# PPR_2_MP.net
KiCad netlist of a schematic drawn in EAGLE
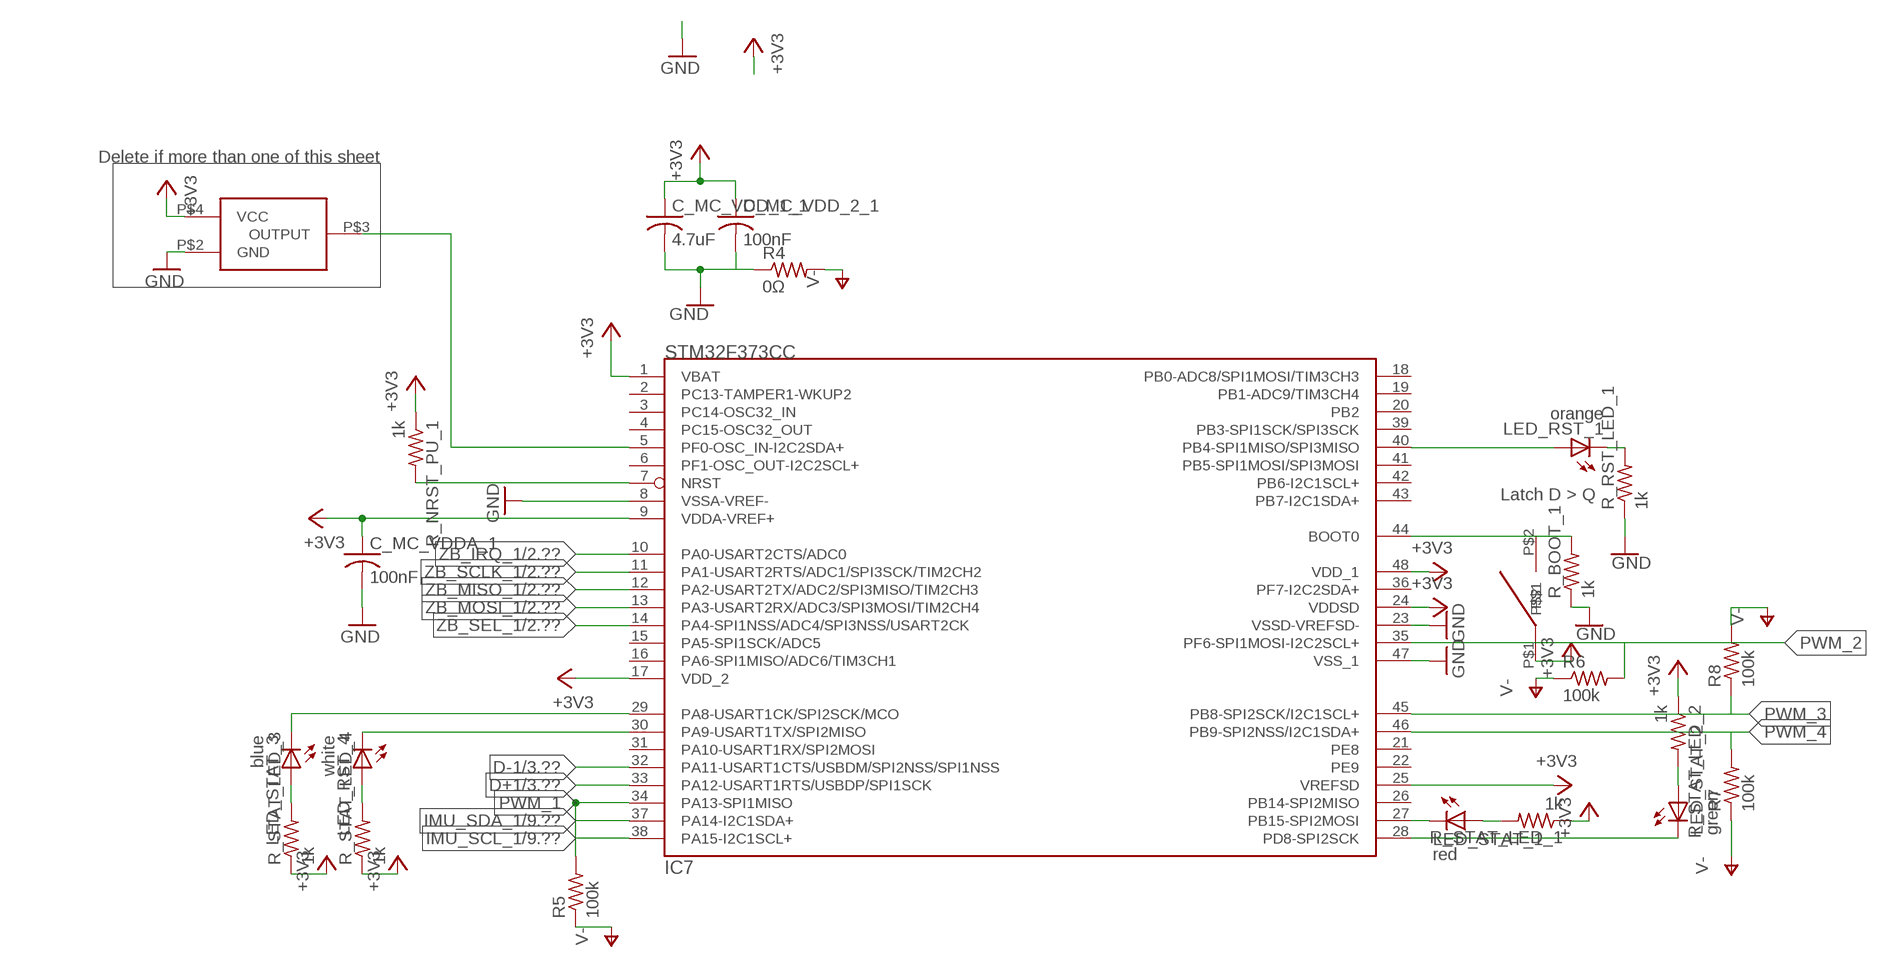
[diagram p0: schematic, sheet 1]
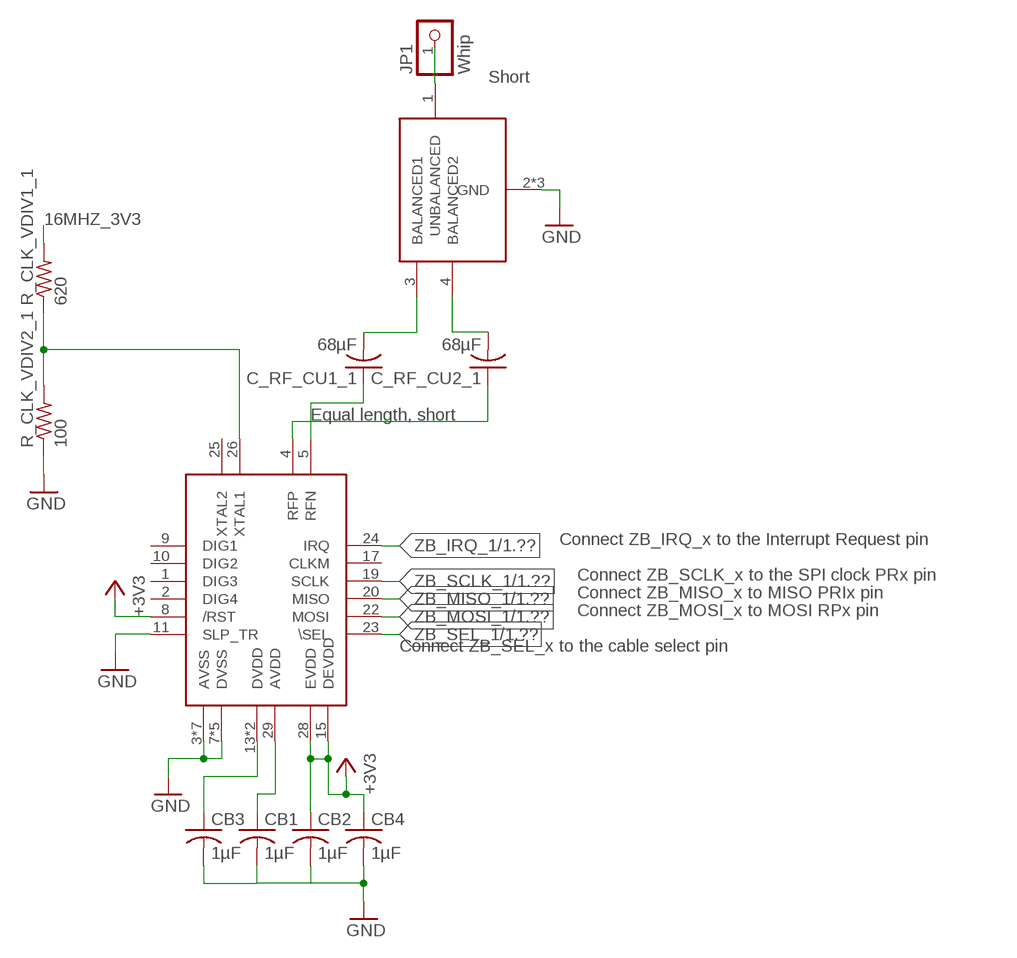
[diagram p1: schematic, sheet 2]
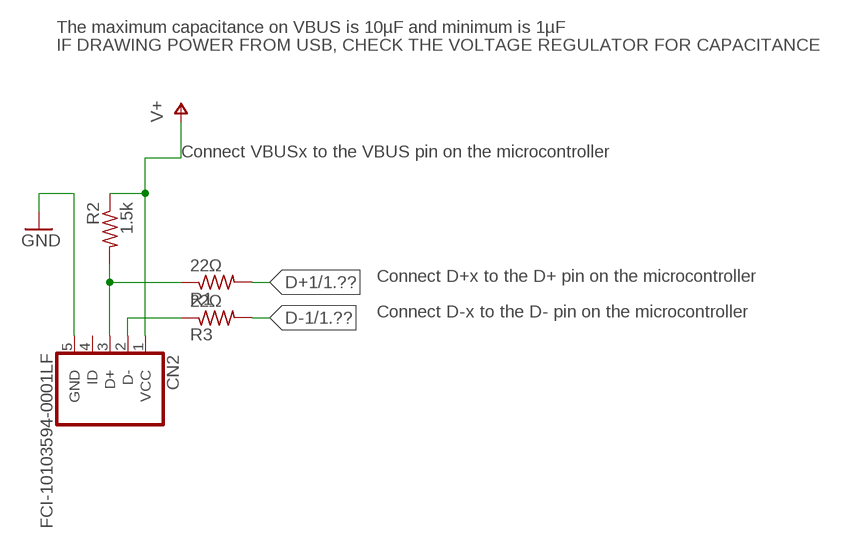
[diagram p2: schematic, sheet 3]
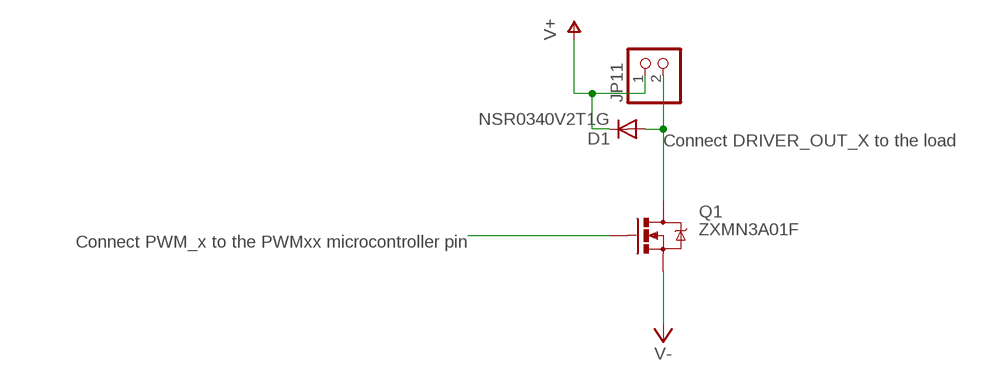
[diagram p3: schematic, sheet 4]
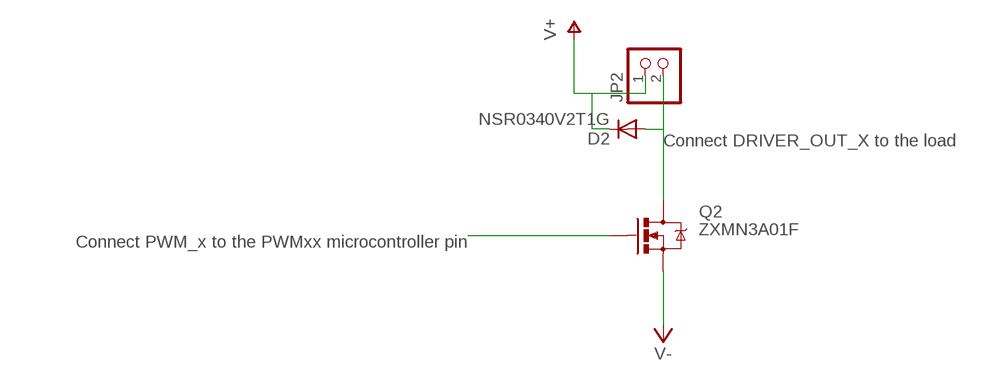
[diagram p4: schematic, sheet 5]
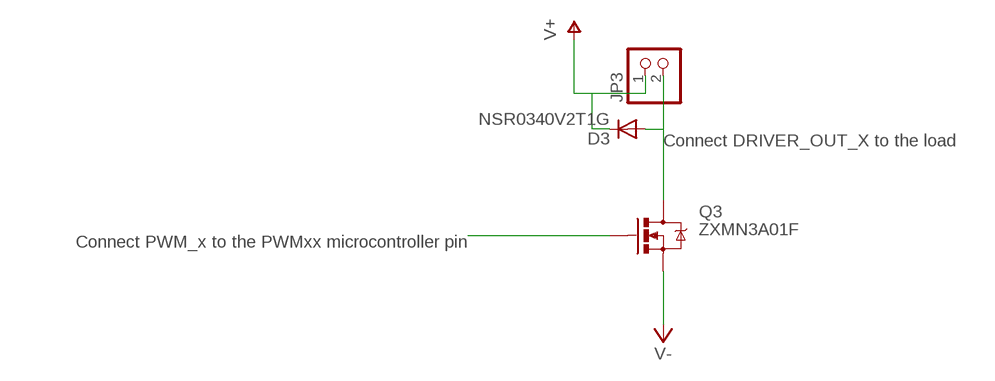
[diagram p5: schematic, sheet 6]
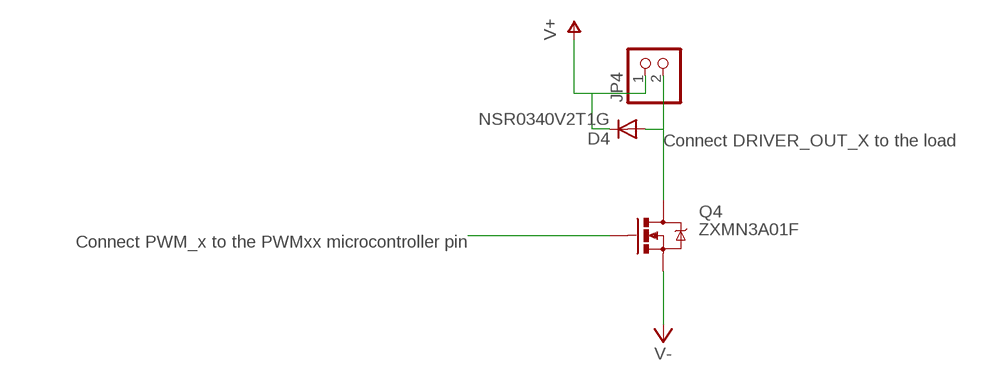
[diagram p6: schematic, sheet 7]
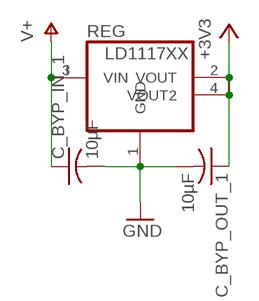
[diagram p7: schematic, sheet 8]
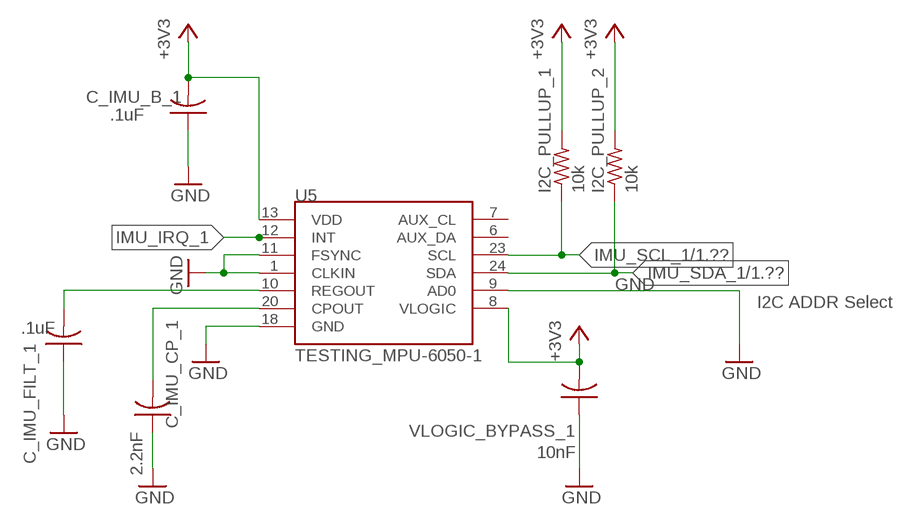
[diagram p8: schematic, sheet 9]
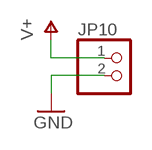
[diagram p9: schematic, sheet 10]

(export (version "E")
  (design (tool "Eeschema 10.0.6"))
  (components
    (comp (ref "C_IMU_B_1")
      (value ".1uF")
      (footprint "eagle-import:C0603")
      (libsource (lib "eagle-import") (part "C-USC0603"))
    )
    (comp (ref "C_IMU_CP_1")
      (value "2.2nF")
      (footprint "eagle-import:C0603")
      (libsource (lib "eagle-import") (part "C-USC0603"))
    )
    (comp (ref "C_IMU_FILT_1")
      (value ".1uF")
      (footprint "eagle-import:C0603")
      (libsource (lib "eagle-import") (part "C-USC0603"))
    )
    (comp (ref "I2C_PULLUP_1")
      (value "10k")
      (footprint "eagle-import:R0402")
      (libsource (lib "eagle-import") (part "R-US_R0402"))
    )
    (comp (ref "I2C_PULLUP_2")
      (value "10k")
      (footprint "eagle-import:R0402")
      (libsource (lib "eagle-import") (part "R-US_R0402"))
    )
    (comp (ref "U5")
      (value "TESTING_MPU-6050-1")
      (footprint "eagle-import:TESTING_QFN-24-4MM2")
      (libsource (lib "eagle-import") (part "TESTING_MPU-6050-1"))
    )
    (comp (ref "VLOGIC_BYPASS_1")
      (value "10nF")
      (footprint "eagle-import:C0603")
      (libsource (lib "eagle-import") (part "C-USC0603"))
    )
    (comp (ref "CN2")
      (value "FCI-10103594-0001LF")
      (footprint "eagle-import:FCI-10103594-0001LF")
      (libsource (lib "eagle-import") (part "USB-RECEPTABLE"))
    )
    (comp (ref "R1")
      (value "22Ω")
      (footprint "eagle-import:R0402")
      (libsource (lib "eagle-import") (part "resistor_R-US_R0402"))
    )
    (comp (ref "R2")
      (value "1.5k")
      (footprint "eagle-import:R0402")
      (libsource (lib "eagle-import") (part "resistor_R-US_R0402"))
    )
    (comp (ref "R3")
      (value "22Ω")
      (footprint "eagle-import:R0402")
      (libsource (lib "eagle-import") (part "resistor_R-US_R0402"))
    )
    (comp (ref "D1")
      (value "NSR0340V2T1G")
      (footprint "eagle-import:SOD523")
      (libsource (lib "eagle-import") (part "DIODE-SOD523"))
    )
    (comp (ref "JP11")
      (value "PINHD-1X2")
      (footprint "eagle-import:1X02")
      (libsource (lib "eagle-import") (part "PINHD-1X2"))
    )
    (comp (ref "Q1")
      (value "ZXMN3A01F")
      (footprint "eagle-import:SOT23-3")
      (libsource (lib "eagle-import") (part "MOSFET-NCHANNELSMD"))
    )
    (comp (ref "D4")
      (value "NSR0340V2T1G")
      (footprint "eagle-import:SOD523")
      (libsource (lib "eagle-import") (part "DIODE-SOD523"))
    )
    (comp (ref "JP4")
      (value "PINHD-1X2")
      (footprint "eagle-import:1X02")
      (libsource (lib "eagle-import") (part "PINHD-1X2"))
    )
    (comp (ref "Q4")
      (value "ZXMN3A01F")
      (footprint "eagle-import:SOT23-3")
      (libsource (lib "eagle-import") (part "MOSFET-NCHANNELSMD"))
    )
    (comp (ref "JP10")
      (value "PINHD-1X2")
      (footprint "eagle-import:1X02")
      (libsource (lib "eagle-import") (part "PINHD-1X2"))
    )
    (comp (ref "C_MC_VDDA_1")
      (value "100nF")
      (footprint "eagle-import:C0603")
      (libsource (lib "eagle-import") (part "C-USC0603"))
    )
    (comp (ref "C_MC_VDD_1_1")
      (value "4.7uF")
      (footprint "eagle-import:C0603")
      (libsource (lib "eagle-import") (part "C-USC0603"))
    )
    (comp (ref "C_MC_VDD_2_1")
      (value "100nF")
      (footprint "eagle-import:C0603")
      (libsource (lib "eagle-import") (part "C-USC0603"))
    )
    (comp (ref "IC7")
      (value "STM32F373CC")
      (footprint "eagle-import:LQFP48")
      (libsource (lib "eagle-import") (part "STM32F373CC"))
    )
    (comp (ref "LED_RST_1")
      (value "orange")
      (footprint "eagle-import:CHIPLED_0603")
      (libsource (lib "eagle-import") (part "LEDCHIPLED_0603"))
    )
    (comp (ref "LED_RST_4")
      (value "white")
      (footprint "eagle-import:CHIPLED_0603")
      (libsource (lib "eagle-import") (part "LEDCHIPLED_0603"))
    )
    (comp (ref "LED_STAT_1")
      (value "red")
      (footprint "eagle-import:CHIPLED_0603")
      (libsource (lib "eagle-import") (part "LEDCHIPLED_0603"))
    )
    (comp (ref "LED_STAT_2")
      (value "green")
      (footprint "eagle-import:CHIPLED_0603")
      (libsource (lib "eagle-import") (part "LEDCHIPLED_0603"))
    )
    (comp (ref "LED_STAT_3")
      (value "blue")
      (footprint "eagle-import:CHIPLED_0603")
      (libsource (lib "eagle-import") (part "LEDCHIPLED_0603"))
    )
    (comp (ref "OSC1")
      (value "FOX924B")
      (footprint "eagle-import:4-SMD_5X3.2")
      (libsource (lib "eagle-import") (part "FOX924B"))
    )
    (comp (ref "R4")
      (value "0Ω")
      (footprint "eagle-import:R0603")
      (libsource (lib "eagle-import") (part "resistor_R-US_R0603"))
    )
    (comp (ref "R5")
      (value "100k")
      (footprint "eagle-import:R0603")
      (libsource (lib "eagle-import") (part "resistor_R-US_R0603"))
    )
    (comp (ref "R6")
      (value "100k")
      (footprint "eagle-import:R0603")
      (libsource (lib "eagle-import") (part "resistor_R-US_R0603"))
    )
    (comp (ref "R7")
      (value "100k")
      (footprint "eagle-import:R0603")
      (libsource (lib "eagle-import") (part "resistor_R-US_R0603"))
    )
    (comp (ref "R8")
      (value "100k")
      (footprint "eagle-import:R0603")
      (libsource (lib "eagle-import") (part "resistor_R-US_R0603"))
    )
    (comp (ref "R_BOOT_1")
      (value "1k")
      (footprint "eagle-import:R0603")
      (libsource (lib "eagle-import") (part "resistor_R-US_R0603"))
    )
    (comp (ref "R_NRST_PU_1")
      (value "1k")
      (footprint "eagle-import:R0603")
      (libsource (lib "eagle-import") (part "resistor_R-US_R0603"))
    )
    (comp (ref "R_RST_LED_1")
      (value "1k")
      (footprint "eagle-import:R0603")
      (libsource (lib "eagle-import") (part "resistor_R-US_R0603"))
    )
    (comp (ref "R_STAT_LED_1")
      (value "1k")
      (footprint "eagle-import:R0603")
      (libsource (lib "eagle-import") (part "resistor_R-US_R0603"))
    )
    (comp (ref "R_STAT_LED_2")
      (value "1k")
      (footprint "eagle-import:R0603")
      (libsource (lib "eagle-import") (part "resistor_R-US_R0603"))
    )
    (comp (ref "R_STAT_LED_3")
      (value "1k")
      (footprint "eagle-import:R0603")
      (libsource (lib "eagle-import") (part "resistor_R-US_R0603"))
    )
    (comp (ref "R_STAT_LED_4")
      (value "1k")
      (footprint "eagle-import:R0603")
      (libsource (lib "eagle-import") (part "resistor_R-US_R0603"))
    )
    (comp (ref "SW1")
      (value "B3U")
      (footprint "eagle-import:B3U")
      (libsource (lib "eagle-import") (part "B3U"))
    )
    (comp (ref "C_BYP_IN_1")
      (value "10µF")
      (footprint "eagle-import:C1206")
      (libsource (lib "eagle-import") (part "C-USC1206"))
    )
    (comp (ref "C_BYP_OUT_1")
      (value "10µF")
      (footprint "eagle-import:C0603")
      (libsource (lib "eagle-import") (part "C-USC0603"))
    )
    (comp (ref "REG")
      (value "LD1117XX")
      (footprint "eagle-import:SOT-223")
      (libsource (lib "eagle-import") (part "LD1117XX"))
    )
    (comp (ref "BALUN1")
      (value "0896FB15A0100")
      (footprint "eagle-import:0896FB15A0100")
      (libsource (lib "eagle-import") (part "0896FB15A0100"))
    )
    (comp (ref "CB1")
      (value "1µF")
      (footprint "eagle-import:C0603")
      (libsource (lib "eagle-import") (part "C-USC0603"))
    )
    (comp (ref "CB2")
      (value "1µF")
      (footprint "eagle-import:C0603")
      (libsource (lib "eagle-import") (part "C-USC0603"))
    )
    (comp (ref "CB3")
      (value "1µF")
      (footprint "eagle-import:C0603")
      (libsource (lib "eagle-import") (part "C-USC0603"))
    )
    (comp (ref "CB4")
      (value "1µF")
      (footprint "eagle-import:C0603")
      (libsource (lib "eagle-import") (part "C-USC0603"))
    )
    (comp (ref "C_RF_CU1_1")
      (value "68µF")
      (footprint "eagle-import:C0603")
      (libsource (lib "eagle-import") (part "C-USC0603"))
    )
    (comp (ref "C_RF_CU2_1")
      (value "68µF")
      (footprint "eagle-import:C0603")
      (libsource (lib "eagle-import") (part "C-USC0603"))
    )
    (comp (ref "JP1")
      (value "Whip")
      (footprint "eagle-import:1X01M")
      (libsource (lib "eagle-import") (part "PINHD-1X01_2.00"))
    )
    (comp (ref "RADIO1")
      (value "AT86RF")
      (footprint "eagle-import:QFNN32")
      (libsource (lib "eagle-import") (part "AT86RF"))
    )
    (comp (ref "R_CLK_VDIV1_1")
      (value "620")
      (footprint "eagle-import:R0603")
      (libsource (lib "eagle-import") (part "resistor_R-US_R0603"))
    )
    (comp (ref "R_CLK_VDIV2_1")
      (value "100")
      (footprint "eagle-import:R0603")
      (libsource (lib "eagle-import") (part "resistor_R-US_R0603"))
    )
    (comp (ref "D3")
      (value "NSR0340V2T1G")
      (footprint "eagle-import:SOD523")
      (libsource (lib "eagle-import") (part "DIODE-SOD523"))
    )
    (comp (ref "JP3")
      (value "PINHD-1X2")
      (footprint "eagle-import:1X02")
      (libsource (lib "eagle-import") (part "PINHD-1X2"))
    )
    (comp (ref "Q3")
      (value "ZXMN3A01F")
      (footprint "eagle-import:SOT23-3")
      (libsource (lib "eagle-import") (part "MOSFET-NCHANNELSMD"))
    )
    (comp (ref "D2")
      (value "NSR0340V2T1G")
      (footprint "eagle-import:SOD523")
      (libsource (lib "eagle-import") (part "DIODE-SOD523"))
    )
    (comp (ref "JP2")
      (value "PINHD-1X2")
      (footprint "eagle-import:1X02")
      (libsource (lib "eagle-import") (part "PINHD-1X2"))
    )
    (comp (ref "Q2")
      (value "ZXMN3A01F")
      (footprint "eagle-import:SOT23-3")
      (libsource (lib "eagle-import") (part "MOSFET-NCHANNELSMD"))
    )
  )
  (nets
    (net (code "1") (name "+3V3") (class "Default")
      (node (ref "CB2") (pin "1") (pinfunction "1_1") (pintype "passive"))
      (node (ref "CB4") (pin "1") (pinfunction "1_1") (pintype "passive"))
      (node (ref "C_BYP_OUT_1") (pin "1") (pinfunction "1_1") (pintype "passive"))
      (node (ref "C_IMU_B_1") (pin "2") (pinfunction "2_2") (pintype "passive"))
      (node (ref "C_MC_VDDA_1") (pin "1") (pinfunction "1_1") (pintype "passive"))
      (node (ref "C_MC_VDD_1_1") (pin "1") (pinfunction "1_1") (pintype "passive"))
      (node (ref "C_MC_VDD_2_1") (pin "1") (pinfunction "1_1") (pintype "passive"))
      (node (ref "I2C_PULLUP_1") (pin "2") (pinfunction "2_2") (pintype "passive"))
      (node (ref "I2C_PULLUP_2") (pin "2") (pinfunction "2_2") (pintype "passive"))
      (node (ref "IC7") (pin "1") (pinfunction "VBAT_1") (pintype "power_in"))
      (node (ref "IC7") (pin "17") (pinfunction "VDD_2_17") (pintype "bidirectional"))
      (node (ref "IC7") (pin "24") (pinfunction "VDDSD_24") (pintype "power_in"))
      (node (ref "IC7") (pin "25") (pinfunction "VREFSD_25") (pintype "bidirectional"))
      (node (ref "IC7") (pin "48") (pinfunction "VDD_1_48") (pintype "power_in"))
      (node (ref "IC7") (pin "9") (pinfunction "VDDA-VREF+_9") (pintype "power_in"))
      (node (ref "OSC1") (pin "P$4") (pinfunction "VCC_P$4") (pintype "bidirectional"))
      (node (ref "RADIO1") (pin "15") (pinfunction "DEVDD_15") (pintype "power_in"))
      (node (ref "RADIO1") (pin "28") (pinfunction "EVDD_28") (pintype "power_in"))
      (node (ref "RADIO1") (pin "8") (pinfunction "/RST_8") (pintype "input"))
      (node (ref "REG") (pin "2") (pinfunction "VOUT_2") (pintype "output"))
      (node (ref "REG") (pin "4") (pinfunction "VOUT2_4") (pintype "output"))
      (node (ref "R_NRST_PU_1") (pin "1") (pinfunction "1_1") (pintype "passive"))
      (node (ref "R_STAT_LED_1") (pin "1") (pinfunction "1_1") (pintype "passive"))
      (node (ref "R_STAT_LED_2") (pin "1") (pinfunction "1_1") (pintype "passive"))
      (node (ref "R_STAT_LED_3") (pin "1") (pinfunction "1_1") (pintype "passive"))
      (node (ref "R_STAT_LED_4") (pin "1") (pinfunction "1_1") (pintype "passive"))
      (node (ref "SW1") (pin "P$1") (pinfunction "P$1_P$1") (pintype "bidirectional"))
      (node (ref "U5") (pin "13") (pinfunction "VDD_13") (pintype "bidirectional"))
      (node (ref "U5") (pin "8") (pinfunction "VLOGIC_8") (pintype "bidirectional"))
      (node (ref "VLOGIC_BYPASS_1") (pin "2") (pinfunction "2_2") (pintype "passive"))
    )
    (net (code "2") (name "16MHZ_3V3") (class "Default")
      (node (ref "IC7") (pin "5") (pinfunction "PF0-OSC_IN-I2C2SDA+_5") (pintype "bidirectional"))
      (node (ref "OSC1") (pin "P$3") (pinfunction "OUTPUT_P$3") (pintype "bidirectional"))
      (node (ref "R_CLK_VDIV1_1") (pin "2") (pinfunction "2_2") (pintype "passive"))
    )
    (net (code "3") (name "D+1") (class "Default")
      (node (ref "IC7") (pin "33") (pinfunction "PA12-USART1RTS/USBDP/SPI1SCK_33") (pintype "bidirectional"))
      (node (ref "R1") (pin "2") (pinfunction "2_2") (pintype "passive"))
    )
    (net (code "4") (name "D-1") (class "Default")
      (node (ref "IC7") (pin "32") (pinfunction "PA11-USART1CTS/USBDM/SPI2NSS/SPI1NSS_32") (pintype "bidirectional"))
      (node (ref "R3") (pin "2") (pinfunction "2_2") (pintype "passive"))
    )
    (net (code "5") (name "GND") (class "Default")
      (node (ref "BALUN1") (pin "2") (pinfunction "GND_2") (pintype "power_in"))
      (node (ref "BALUN1") (pin "5") (pinfunction "GND_5") (pintype "power_in"))
      (node (ref "BALUN1") (pin "6") (pinfunction "GND_6") (pintype "power_in"))
      (node (ref "CB1") (pin "2") (pinfunction "2_2") (pintype "passive"))
      (node (ref "CB2") (pin "2") (pinfunction "2_2") (pintype "passive"))
      (node (ref "CB3") (pin "2") (pinfunction "2_2") (pintype "passive"))
      (node (ref "CB4") (pin "2") (pinfunction "2_2") (pintype "passive"))
      (node (ref "CN2") (pin "5") (pinfunction "GND_5") (pintype "bidirectional"))
      (node (ref "C_BYP_IN_1") (pin "2") (pinfunction "2_2") (pintype "passive"))
      (node (ref "C_BYP_OUT_1") (pin "2") (pinfunction "2_2") (pintype "passive"))
      (node (ref "C_IMU_B_1") (pin "1") (pinfunction "1_1") (pintype "passive"))
      (node (ref "C_IMU_CP_1") (pin "1") (pinfunction "1_1") (pintype "passive"))
      (node (ref "C_IMU_FILT_1") (pin "1") (pinfunction "1_1") (pintype "passive"))
      (node (ref "C_MC_VDDA_1") (pin "2") (pinfunction "2_2") (pintype "passive"))
      (node (ref "C_MC_VDD_1_1") (pin "2") (pinfunction "2_2") (pintype "passive"))
      (node (ref "C_MC_VDD_2_1") (pin "2") (pinfunction "2_2") (pintype "passive"))
      (node (ref "IC7") (pin "23") (pinfunction "VSSD-VREFSD-_23") (pintype "power_in"))
      (node (ref "IC7") (pin "47") (pinfunction "VSS_1_47") (pintype "power_in"))
      (node (ref "IC7") (pin "8") (pinfunction "VSSA-VREF-_8") (pintype "power_in"))
      (node (ref "JP10") (pin "2") (pinfunction "2_2") (pintype "passive"))
      (node (ref "OSC1") (pin "P$2") (pinfunction "GND_P$2") (pintype "bidirectional"))
      (node (ref "R4") (pin "1") (pinfunction "1_1") (pintype "passive"))
      (node (ref "RADIO1") (pin "11") (pinfunction "SLP_TR_11") (pintype "bidirectional"))
      (node (ref "RADIO1") (pin "12") (pinfunction "DVSS_12") (pintype "power_in"))
      (node (ref "RADIO1") (pin "16") (pinfunction "DVSS_16") (pintype "power_in"))
      (node (ref "RADIO1") (pin "18") (pinfunction "DVSS_18") (pintype "power_in"))
      (node (ref "RADIO1") (pin "21") (pinfunction "DVSS_21") (pintype "power_in"))
      (node (ref "RADIO1") (pin "27") (pinfunction "AVSS_27") (pintype "power_in"))
      (node (ref "RADIO1") (pin "3") (pinfunction "AVSS_3") (pintype "power_in"))
      (node (ref "RADIO1") (pin "30") (pinfunction "AVSS_30") (pintype "power_in"))
      (node (ref "RADIO1") (pin "31") (pinfunction "AVSS_31") (pintype "power_in"))
      (node (ref "RADIO1") (pin "32") (pinfunction "AVSS_32") (pintype "power_in"))
      (node (ref "RADIO1") (pin "6") (pinfunction "AVSS_6") (pintype "power_in"))
      (node (ref "RADIO1") (pin "7") (pinfunction "DVSS_7") (pintype "power_in"))
      (node (ref "RADIO1") (pin "EXP") (pinfunction "AVSS_EXP") (pintype "power_in"))
      (node (ref "REG") (pin "1") (pinfunction "GND_1") (pintype "power_in"))
      (node (ref "R_BOOT_1") (pin "1") (pinfunction "1_1") (pintype "passive"))
      (node (ref "R_CLK_VDIV2_1") (pin "1") (pinfunction "1_1") (pintype "passive"))
      (node (ref "R_RST_LED_1") (pin "1") (pinfunction "1_1") (pintype "passive"))
      (node (ref "U5") (pin "1") (pinfunction "CLKIN_1") (pintype "bidirectional"))
      (node (ref "U5") (pin "11") (pinfunction "FSYNC_11") (pintype "bidirectional"))
      (node (ref "U5") (pin "18") (pinfunction "GND_18") (pintype "bidirectional"))
      (node (ref "U5") (pin "9") (pinfunction "AD0_9") (pintype "bidirectional"))
      (node (ref "VLOGIC_BYPASS_1") (pin "1") (pinfunction "1_1") (pintype "passive"))
    )
    (net (code "6") (name "IMU_IRQ_1") (class "Default")
      (node (ref "U5") (pin "12") (pinfunction "INT_12") (pintype "bidirectional"))
    )
    (net (code "7") (name "IMU_SCL_1") (class "Default")
      (node (ref "I2C_PULLUP_1") (pin "1") (pinfunction "1_1") (pintype "passive"))
      (node (ref "IC7") (pin "38") (pinfunction "PA15-I2C1SCL+_38") (pintype "bidirectional"))
      (node (ref "U5") (pin "23") (pinfunction "SCL_23") (pintype "bidirectional"))
    )
    (net (code "8") (name "IMU_SDA_1") (class "Default")
      (node (ref "I2C_PULLUP_2") (pin "1") (pinfunction "1_1") (pintype "passive"))
      (node (ref "IC7") (pin "37") (pinfunction "PA14-I2C1SDA+_37") (pintype "bidirectional"))
      (node (ref "U5") (pin "24") (pinfunction "SDA_24") (pintype "bidirectional"))
    )
    (net (code "9") (name "Net-(BALUN1-BALANCED1)") (class "Default")
      (node (ref "BALUN1") (pin "3") (pinfunction "BALANCED1_3") (pintype "bidirectional"))
      (node (ref "C_RF_CU1_1") (pin "2") (pinfunction "2_2") (pintype "passive"))
    )
    (net (code "10") (name "Net-(BALUN1-BALANCED2)") (class "Default")
      (node (ref "BALUN1") (pin "4") (pinfunction "BALANCED2_4") (pintype "bidirectional"))
      (node (ref "C_RF_CU2_1") (pin "2") (pinfunction "2_2") (pintype "passive"))
    )
    (net (code "11") (name "Net-(BALUN1-UNBALANCED)") (class "Default")
      (node (ref "BALUN1") (pin "1") (pinfunction "UNBALANCED_1") (pintype "bidirectional"))
      (node (ref "JP1") (pin "1") (pinfunction "1_1") (pintype "passive"))
    )
    (net (code "12") (name "Net-(CB3-Pad1)") (class "Default")
      (node (ref "CB3") (pin "1") (pinfunction "1_1") (pintype "passive"))
      (node (ref "RADIO1") (pin "13") (pinfunction "DVDD_13") (pintype "power_in"))
      (node (ref "RADIO1") (pin "14") (pinfunction "DVDD_14") (pintype "power_in"))
    )
    (net (code "13") (name "Net-(CN2-D+)") (class "Default")
      (node (ref "CN2") (pin "3") (pinfunction "D+_3") (pintype "bidirectional"))
      (node (ref "R1") (pin "1") (pinfunction "1_1") (pintype "passive"))
      (node (ref "R2") (pin "2") (pinfunction "2_2") (pintype "passive"))
    )
    (net (code "14") (name "Net-(CN2-D-)") (class "Default")
      (node (ref "CN2") (pin "2") (pinfunction "D-_2") (pintype "bidirectional"))
      (node (ref "R3") (pin "1") (pinfunction "1_1") (pintype "passive"))
    )
    (net (code "15") (name "Net-(IC7-BOOT0)") (class "Default")
      (node (ref "IC7") (pin "44") (pinfunction "BOOT0_44") (pintype "input"))
      (node (ref "R_BOOT_1") (pin "2") (pinfunction "2_2") (pintype "passive"))
      (node (ref "SW1") (pin "P$2") (pinfunction "P$2_P$2") (pintype "bidirectional"))
    )
    (net (code "16") (name "Net-(IC7-NRST)") (class "Default")
      (node (ref "IC7") (pin "7") (pinfunction "NRST_7") (pintype "bidirectional"))
      (node (ref "R_NRST_PU_1") (pin "2") (pinfunction "2_2") (pintype "passive"))
    )
    (net (code "17") (name "Net-(IC7-PA8-USART1CK{slash}SPI2SCK{slash}MCO)") (class "Default")
      (node (ref "IC7") (pin "29") (pinfunction "PA8-USART1CK/SPI2SCK/MCO_29") (pintype "bidirectional"))
      (node (ref "LED_STAT_3") (pin "C") (pinfunction "C_C") (pintype "passive"))
    )
    (net (code "18") (name "Net-(IC7-PA9-USART1TX{slash}SPI2MISO)") (class "Default")
      (node (ref "IC7") (pin "30") (pinfunction "PA9-USART1TX/SPI2MISO_30") (pintype "bidirectional"))
      (node (ref "LED_RST_4") (pin "C") (pinfunction "C_C") (pintype "passive"))
    )
    (net (code "19") (name "Net-(IC7-PB4-SPI1MISO{slash}SPI3MISO)") (class "Default")
      (node (ref "IC7") (pin "40") (pinfunction "PB4-SPI1MISO/SPI3MISO_40") (pintype "bidirectional"))
      (node (ref "LED_RST_1") (pin "A") (pinfunction "A_A") (pintype "passive"))
    )
    (net (code "20") (name "Net-(IC7-PB15-SPI2MOSI)") (class "Default")
      (node (ref "IC7") (pin "27") (pinfunction "PB15-SPI2MOSI_27") (pintype "bidirectional"))
      (node (ref "LED_STAT_1") (pin "C") (pinfunction "C_C") (pintype "passive"))
    )
    (net (code "21") (name "Net-(IC7-PD8-SPI2SCK)") (class "Default")
      (node (ref "IC7") (pin "28") (pinfunction "PD8-SPI2SCK_28") (pintype "bidirectional"))
      (node (ref "LED_STAT_2") (pin "C") (pinfunction "C_C") (pintype "passive"))
    )
    (net (code "22") (name "Net-(LED_RST_1-PadC)") (class "Default")
      (node (ref "LED_RST_1") (pin "C") (pinfunction "C_C") (pintype "passive"))
      (node (ref "R_RST_LED_1") (pin "2") (pinfunction "2_2") (pintype "passive"))
    )
    (net (code "23") (name "Net-(LED_RST_4-PadA)") (class "Default")
      (node (ref "LED_RST_4") (pin "A") (pinfunction "A_A") (pintype "passive"))
      (node (ref "R_STAT_LED_4") (pin "2") (pinfunction "2_2") (pintype "passive"))
    )
    (net (code "24") (name "Net-(LED_STAT_1-PadA)") (class "Default")
      (node (ref "LED_STAT_1") (pin "A") (pinfunction "A_A") (pintype "passive"))
      (node (ref "R_STAT_LED_1") (pin "2") (pinfunction "2_2") (pintype "passive"))
    )
    (net (code "25") (name "Net-(LED_STAT_2-PadA)") (class "Default")
      (node (ref "LED_STAT_2") (pin "A") (pinfunction "A_A") (pintype "passive"))
      (node (ref "R_STAT_LED_2") (pin "2") (pinfunction "2_2") (pintype "passive"))
    )
    (net (code "26") (name "Net-(LED_STAT_3-PadA)") (class "Default")
      (node (ref "LED_STAT_3") (pin "A") (pinfunction "A_A") (pintype "passive"))
      (node (ref "R_STAT_LED_3") (pin "2") (pinfunction "2_2") (pintype "passive"))
    )
    (net (code "27") (name "Net-(Q1-D)") (class "Default")
      (node (ref "D1") (pin "A") (pinfunction "A_A") (pintype "passive"))
      (node (ref "JP11") (pin "2") (pinfunction "2_2") (pintype "passive"))
      (node (ref "Q1") (pin "3") (pinfunction "D_3") (pintype "passive"))
    )
    (net (code "28") (name "Net-(Q2-D)") (class "Default")
      (node (ref "D2") (pin "A") (pinfunction "A_A") (pintype "passive"))
      (node (ref "JP2") (pin "2") (pinfunction "2_2") (pintype "passive"))
      (node (ref "Q2") (pin "3") (pinfunction "D_3") (pintype "passive"))
    )
    (net (code "29") (name "Net-(Q3-D)") (class "Default")
      (node (ref "D3") (pin "A") (pinfunction "A_A") (pintype "passive"))
      (node (ref "JP3") (pin "2") (pinfunction "2_2") (pintype "passive"))
      (node (ref "Q3") (pin "3") (pinfunction "D_3") (pintype "passive"))
    )
    (net (code "30") (name "Net-(Q4-D)") (class "Default")
      (node (ref "D4") (pin "A") (pinfunction "A_A") (pintype "passive"))
      (node (ref "JP4") (pin "2") (pinfunction "2_2") (pintype "passive"))
      (node (ref "Q4") (pin "3") (pinfunction "D_3") (pintype "passive"))
    )
    (net (code "31") (name "Net-(RADIO1-AVDD)") (class "Default")
      (node (ref "CB1") (pin "1") (pinfunction "1_1") (pintype "passive"))
      (node (ref "RADIO1") (pin "29") (pinfunction "AVDD_29") (pintype "power_in"))
    )
    (net (code "32") (name "Net-(RADIO1-RFN)") (class "Default")
      (node (ref "C_RF_CU1_1") (pin "1") (pinfunction "1_1") (pintype "passive"))
      (node (ref "RADIO1") (pin "5") (pinfunction "RFN_5") (pintype "bidirectional"))
    )
    (net (code "33") (name "Net-(RADIO1-RFP)") (class "Default")
      (node (ref "C_RF_CU2_1") (pin "1") (pinfunction "1_1") (pintype "passive"))
      (node (ref "RADIO1") (pin "4") (pinfunction "RFP_4") (pintype "bidirectional"))
    )
    (net (code "34") (name "Net-(RADIO1-XTAL1)") (class "Default")
      (node (ref "RADIO1") (pin "26") (pinfunction "XTAL1_26") (pintype "bidirectional"))
      (node (ref "R_CLK_VDIV1_1") (pin "1") (pinfunction "1_1") (pintype "passive"))
      (node (ref "R_CLK_VDIV2_1") (pin "2") (pinfunction "2_2") (pintype "passive"))
    )
    (net (code "35") (name "Net-(U5-CPOUT)") (class "Default")
      (node (ref "C_IMU_CP_1") (pin "2") (pinfunction "2_2") (pintype "passive"))
      (node (ref "U5") (pin "20") (pinfunction "CPOUT_20") (pintype "bidirectional"))
    )
    (net (code "36") (name "Net-(U5-REGOUT)") (class "Default")
      (node (ref "C_IMU_FILT_1") (pin "2") (pinfunction "2_2") (pintype "passive"))
      (node (ref "U5") (pin "10") (pinfunction "REGOUT_10") (pintype "bidirectional"))
    )
    (net (code "37") (name "PWM_1") (class "Default")
      (node (ref "IC7") (pin "34") (pinfunction "PA13-SPI1MISO_34") (pintype "bidirectional"))
      (node (ref "Q1") (pin "1") (pinfunction "G_1") (pintype "passive"))
      (node (ref "R5") (pin "2") (pinfunction "2_2") (pintype "passive"))
    )
    (net (code "38") (name "PWM_2") (class "Default")
      (node (ref "IC7") (pin "35") (pinfunction "PF6-SPI1MOSI-I2C2SCL+_35") (pintype "bidirectional"))
      (node (ref "Q2") (pin "1") (pinfunction "G_1") (pintype "passive"))
      (node (ref "R6") (pin "2") (pinfunction "2_2") (pintype "passive"))
    )
    (net (code "39") (name "PWM_3") (class "Default")
      (node (ref "IC7") (pin "45") (pinfunction "PB8-SPI2SCK/I2C1SCL+_45") (pintype "bidirectional"))
      (node (ref "Q3") (pin "1") (pinfunction "G_1") (pintype "passive"))
      (node (ref "R8") (pin "1") (pinfunction "1_1") (pintype "passive"))
    )
    (net (code "40") (name "PWM_4") (class "Default")
      (node (ref "IC7") (pin "46") (pinfunction "PB9-SPI2NSS/I2C1SDA+_46") (pintype "bidirectional"))
      (node (ref "Q4") (pin "1") (pinfunction "G_1") (pintype "passive"))
      (node (ref "R7") (pin "2") (pinfunction "2_2") (pintype "passive"))
    )
    (net (code "41") (name "V+") (class "Default")
      (node (ref "CN2") (pin "1") (pinfunction "VCC_1") (pintype "bidirectional"))
      (node (ref "C_BYP_IN_1") (pin "1") (pinfunction "1_1") (pintype "passive"))
      (node (ref "D1") (pin "C") (pinfunction "C_C") (pintype "passive"))
      (node (ref "D2") (pin "C") (pinfunction "C_C") (pintype "passive"))
      (node (ref "D3") (pin "C") (pinfunction "C_C") (pintype "passive"))
      (node (ref "D4") (pin "C") (pinfunction "C_C") (pintype "passive"))
      (node (ref "JP10") (pin "1") (pinfunction "1_1") (pintype "passive"))
      (node (ref "JP11") (pin "1") (pinfunction "1_1") (pintype "passive"))
      (node (ref "JP2") (pin "1") (pinfunction "1_1") (pintype "passive"))
      (node (ref "JP3") (pin "1") (pinfunction "1_1") (pintype "passive"))
      (node (ref "JP4") (pin "1") (pinfunction "1_1") (pintype "passive"))
      (node (ref "R2") (pin "1") (pinfunction "1_1") (pintype "passive"))
      (node (ref "REG") (pin "3") (pinfunction "VIN_3") (pintype "input"))
    )
    (net (code "42") (name "V-") (class "Default")
      (node (ref "Q1") (pin "2") (pinfunction "S_2") (pintype "passive"))
      (node (ref "Q2") (pin "2") (pinfunction "S_2") (pintype "passive"))
      (node (ref "Q3") (pin "2") (pinfunction "S_2") (pintype "passive"))
      (node (ref "Q4") (pin "2") (pinfunction "S_2") (pintype "passive"))
      (node (ref "R4") (pin "2") (pinfunction "2_2") (pintype "passive"))
      (node (ref "R5") (pin "1") (pinfunction "1_1") (pintype "passive"))
      (node (ref "R6") (pin "1") (pinfunction "1_1") (pintype "passive"))
      (node (ref "R7") (pin "1") (pinfunction "1_1") (pintype "passive"))
      (node (ref "R8") (pin "2") (pinfunction "2_2") (pintype "passive"))
    )
    (net (code "43") (name "ZB_IRQ_1") (class "Default")
      (node (ref "IC7") (pin "10") (pinfunction "PA0-USART2CTS/ADC0_10") (pintype "bidirectional"))
      (node (ref "RADIO1") (pin "24") (pinfunction "IRQ_24") (pintype "output"))
    )
    (net (code "44") (name "ZB_MISO_1") (class "Default")
      (node (ref "IC7") (pin "12") (pinfunction "PA2-USART2TX/ADC2/SPI3MISO/TIM2CH3_12") (pintype "bidirectional"))
      (node (ref "RADIO1") (pin "20") (pinfunction "MISO_20") (pintype "output"))
    )
    (net (code "45") (name "ZB_MOSI_1") (class "Default")
      (node (ref "IC7") (pin "13") (pinfunction "PA3-USART2RX/ADC3/SPI3MOSI/TIM2CH4_13") (pintype "bidirectional"))
      (node (ref "RADIO1") (pin "22") (pinfunction "MOSI_22") (pintype "input"))
    )
    (net (code "46") (name "ZB_SCLK_1") (class "Default")
      (node (ref "IC7") (pin "11") (pinfunction "PA1-USART2RTS/ADC1/SPI3SCK/TIM2CH2_11") (pintype "bidirectional"))
      (node (ref "RADIO1") (pin "19") (pinfunction "SCLK_19") (pintype "input"))
    )
    (net (code "47") (name "ZB_SEL_1") (class "Default")
      (node (ref "IC7") (pin "14") (pinfunction "PA4-SPI1NSS/ADC4/SPI3NSS/USART2CK_14") (pintype "bidirectional"))
      (node (ref "RADIO1") (pin "23") (pinfunction "\\SEL_23") (pintype "input"))
    )
    (net (code "48") (name "unconnected-(CN2-ID-Pad4)") (class "Default")
      (node (ref "CN2") (pin "4") (pinfunction "ID_4") (pintype "bidirectional"))
    )
    (net (code "49") (name "unconnected-(IC7-PA5-SPI1SCK{slash}ADC5-Pad15)") (class "Default")
      (node (ref "IC7") (pin "15") (pinfunction "PA5-SPI1SCK/ADC5_15") (pintype "bidirectional"))
    )
    (net (code "50") (name "unconnected-(IC7-PA6-SPI1MISO{slash}ADC6{slash}TIM3CH1-Pad16)") (class "Default")
      (node (ref "IC7") (pin "16") (pinfunction "PA6-SPI1MISO/ADC6/TIM3CH1_16") (pintype "bidirectional"))
    )
    (net (code "51") (name "unconnected-(IC7-PA10-USART1RX{slash}SPI2MOSI-Pad31)") (class "Default")
      (node (ref "IC7") (pin "31") (pinfunction "PA10-USART1RX/SPI2MOSI_31") (pintype "bidirectional"))
    )
    (net (code "52") (name "unconnected-(IC7-PB0-ADC8{slash}SPI1MOSI{slash}TIM3CH3-Pad18)") (class "Default")
      (node (ref "IC7") (pin "18") (pinfunction "PB0-ADC8/SPI1MOSI/TIM3CH3_18") (pintype "bidirectional"))
    )
    (net (code "53") (name "unconnected-(IC7-PB1-ADC9{slash}TIM3CH4-Pad19)") (class "Default")
      (node (ref "IC7") (pin "19") (pinfunction "PB1-ADC9/TIM3CH4_19") (pintype "bidirectional"))
    )
    (net (code "54") (name "unconnected-(IC7-PB2-Pad20)") (class "Default")
      (node (ref "IC7") (pin "20") (pinfunction "PB2_20") (pintype "bidirectional"))
    )
    (net (code "55") (name "unconnected-(IC7-PB3-SPI1SCK{slash}SPI3SCK-Pad39)") (class "Default")
      (node (ref "IC7") (pin "39") (pinfunction "PB3-SPI1SCK/SPI3SCK_39") (pintype "bidirectional"))
    )
    (net (code "56") (name "unconnected-(IC7-PB5-SPI1MOSI{slash}SPI3MOSI-Pad41)") (class "Default")
      (node (ref "IC7") (pin "41") (pinfunction "PB5-SPI1MOSI/SPI3MOSI_41") (pintype "bidirectional"))
    )
    (net (code "57") (name "unconnected-(IC7-PB6-I2C1SCL+-Pad42)") (class "Default")
      (node (ref "IC7") (pin "42") (pinfunction "PB6-I2C1SCL+_42") (pintype "bidirectional"))
    )
    (net (code "58") (name "unconnected-(IC7-PB7-I2C1SDA+-Pad43)") (class "Default")
      (node (ref "IC7") (pin "43") (pinfunction "PB7-I2C1SDA+_43") (pintype "bidirectional"))
    )
    (net (code "59") (name "unconnected-(IC7-PB14-SPI2MISO-Pad26)") (class "Default")
      (node (ref "IC7") (pin "26") (pinfunction "PB14-SPI2MISO_26") (pintype "bidirectional"))
    )
    (net (code "60") (name "unconnected-(IC7-PC13-TAMPER1-WKUP2-Pad2)") (class "Default")
      (node (ref "IC7") (pin "2") (pinfunction "PC13-TAMPER1-WKUP2_2") (pintype "bidirectional"))
    )
    (net (code "61") (name "unconnected-(IC7-PC14-OSC32_IN-Pad3)") (class "Default")
      (node (ref "IC7") (pin "3") (pinfunction "PC14-OSC32_IN_3") (pintype "bidirectional"))
    )
    (net (code "62") (name "unconnected-(IC7-PC15-OSC32_OUT-Pad4)") (class "Default")
      (node (ref "IC7") (pin "4") (pinfunction "PC15-OSC32_OUT_4") (pintype "bidirectional"))
    )
    (net (code "63") (name "unconnected-(IC7-PE8-Pad21)") (class "Default")
      (node (ref "IC7") (pin "21") (pinfunction "PE8_21") (pintype "bidirectional"))
    )
    (net (code "64") (name "unconnected-(IC7-PE9-Pad22)") (class "Default")
      (node (ref "IC7") (pin "22") (pinfunction "PE9_22") (pintype "bidirectional"))
    )
    (net (code "65") (name "unconnected-(IC7-PF1-OSC_OUT-I2C2SCL+-Pad6)") (class "Default")
      (node (ref "IC7") (pin "6") (pinfunction "PF1-OSC_OUT-I2C2SCL+_6") (pintype "bidirectional"))
    )
    (net (code "66") (name "unconnected-(IC7-PF7-I2C2SDA+-Pad36)") (class "Default")
      (node (ref "IC7") (pin "36") (pinfunction "PF7-I2C2SDA+_36") (pintype "bidirectional"))
    )
    (net (code "67") (name "unconnected-(RADIO1-CLKM-Pad17)") (class "Default")
      (node (ref "RADIO1") (pin "17") (pinfunction "CLKM_17") (pintype "output"))
    )
    (net (code "68") (name "unconnected-(RADIO1-DIG1-Pad9)") (class "Default")
      (node (ref "RADIO1") (pin "9") (pinfunction "DIG1_9") (pintype "output"))
    )
    (net (code "69") (name "unconnected-(RADIO1-DIG2-Pad10)") (class "Default")
      (node (ref "RADIO1") (pin "10") (pinfunction "DIG2_10") (pintype "output"))
    )
    (net (code "70") (name "unconnected-(RADIO1-DIG3-Pad1)") (class "Default")
      (node (ref "RADIO1") (pin "1") (pinfunction "DIG3_1") (pintype "output"))
    )
    (net (code "71") (name "unconnected-(RADIO1-DIG4-Pad2)") (class "Default")
      (node (ref "RADIO1") (pin "2") (pinfunction "DIG4_2") (pintype "output"))
    )
    (net (code "72") (name "unconnected-(RADIO1-XTAL2-Pad25)") (class "Default")
      (node (ref "RADIO1") (pin "25") (pinfunction "XTAL2_25") (pintype "bidirectional"))
    )
    (net (code "73") (name "unconnected-(U5-AUX_CL-Pad7)") (class "Default")
      (node (ref "U5") (pin "7") (pinfunction "AUX_CL_7") (pintype "bidirectional"))
    )
    (net (code "74") (name "unconnected-(U5-AUX_DA-Pad6)") (class "Default")
      (node (ref "U5") (pin "6") (pinfunction "AUX_DA_6") (pintype "bidirectional"))
    )
  )
)
